# Modular_Link_PCB.net
KiCad netlist of a schematic drawn in EAGLE
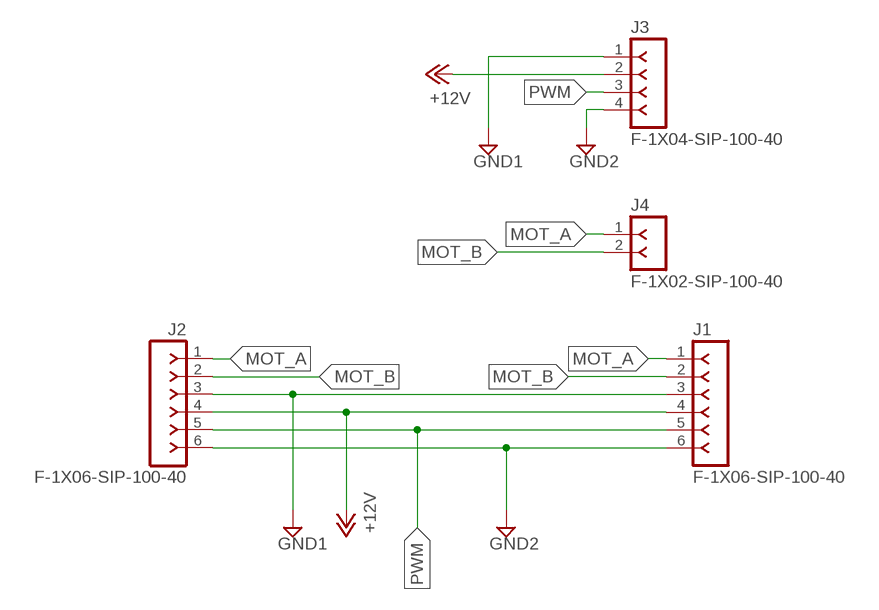
[diagram p0: schematic, sheet 1]

(export (version "E")
  (design (tool "Eeschema 10.0.6"))
  (components
    (comp (ref "J1")
      (value "F-1X06-SIP-100-40")
      (footprint "eagle-import:SIP-100-06-40")
      (libsource (lib "eagle-import") (part "F-1X06-SIP-100-40"))
    )
    (comp (ref "J2")
      (value "F-1X06-SIP-100-40")
      (footprint "eagle-import:SIP-100-06-40")
      (libsource (lib "eagle-import") (part "F-1X06-SIP-100-40"))
    )
    (comp (ref "J3")
      (value "F-1X04-SIP-100-40")
      (footprint "eagle-import:SIP-100-04-40")
      (libsource (lib "eagle-import") (part "F-1X04-SIP-100-40"))
    )
    (comp (ref "J4")
      (value "F-1X02-SIP-100-40")
      (footprint "eagle-import:SIP-100-02-40")
      (libsource (lib "eagle-import") (part "F-1X02-SIP-100-40"))
    )
  )
  (nets
    (net (code "1") (name "+12V") (class "Default")
      (node (ref "J1") (pin "4") (pinfunction "4_4") (pintype "passive"))
      (node (ref "J2") (pin "4") (pinfunction "4_4") (pintype "passive"))
      (node (ref "J3") (pin "2") (pinfunction "2_2") (pintype "passive"))
    )
    (net (code "2") (name "GND1") (class "Default")
      (node (ref "J1") (pin "3") (pinfunction "3_3") (pintype "passive"))
      (node (ref "J2") (pin "3") (pinfunction "3_3") (pintype "passive"))
      (node (ref "J3") (pin "1") (pinfunction "1_1") (pintype "passive"))
    )
    (net (code "3") (name "GND2") (class "Default")
      (node (ref "J1") (pin "6") (pinfunction "6_6") (pintype "passive"))
      (node (ref "J2") (pin "6") (pinfunction "6_6") (pintype "passive"))
      (node (ref "J3") (pin "4") (pinfunction "4_4") (pintype "passive"))
    )
    (net (code "4") (name "MOT_A") (class "Default")
      (node (ref "J1") (pin "1") (pinfunction "1_1") (pintype "passive"))
      (node (ref "J2") (pin "1") (pinfunction "1_1") (pintype "passive"))
      (node (ref "J4") (pin "1") (pinfunction "1_1") (pintype "passive"))
    )
    (net (code "5") (name "MOT_B") (class "Default")
      (node (ref "J1") (pin "2") (pinfunction "2_2") (pintype "passive"))
      (node (ref "J2") (pin "2") (pinfunction "2_2") (pintype "passive"))
      (node (ref "J4") (pin "2") (pinfunction "2_2") (pintype "passive"))
    )
    (net (code "6") (name "PWM") (class "Default")
      (node (ref "J1") (pin "5") (pinfunction "5_5") (pintype "passive"))
      (node (ref "J2") (pin "5") (pinfunction "5_5") (pintype "passive"))
      (node (ref "J3") (pin "3") (pinfunction "3_3") (pintype "passive"))
    )
  )
)
